# Sheet5.net
KiCad netlist of a schematic drawn in Altium Designer
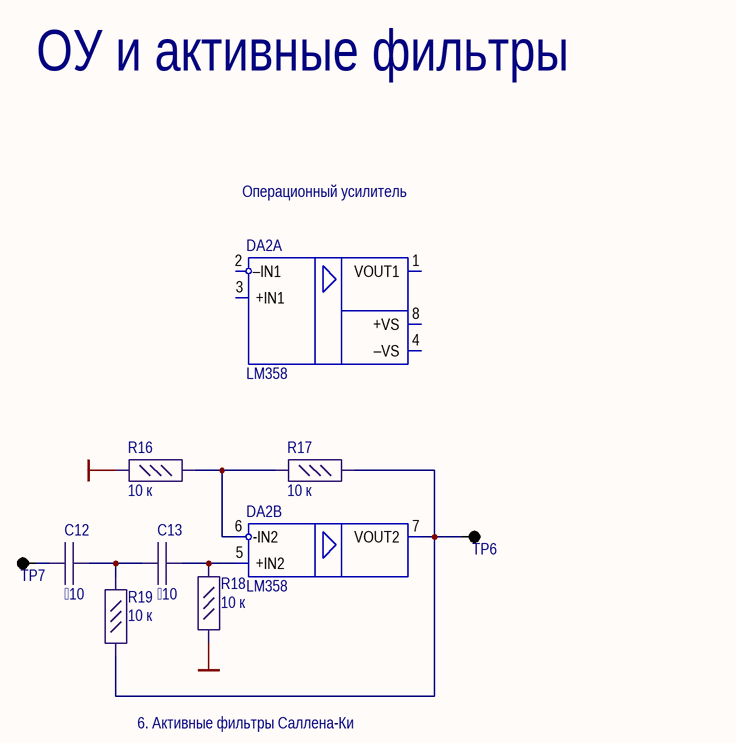
[diagram p0: Sheet5.SchDoc]

(export (version "E")
  (design (tool "Eeschema 10.0.6"))
  (components
    (comp (ref "C12")
      (value "10")
      (footprint "C_0603")
      (description "CAP CER 0.1UF 100V X7R 0603")
      (fields
        (field (name "PART NUMBER") "GRM188R72A104KA35D")
        (field (name "MANUFACTURER") "Murata Electronics")
      )
      (libsource (lib "Database_Lib") (part "Capasitor"))
    )
    (comp (ref "C13")
      (value "10")
      (footprint "C_0603")
      (description "CAP CER 0.1UF 100V X7R 0603")
      (fields
        (field (name "PART NUMBER") "GRM188R72A104KA35D")
        (field (name "MANUFACTURER") "Murata Electronics")
      )
      (libsource (lib "Database_Lib") (part "Capasitor"))
    )
    (comp (ref "DA2") (value "LM358") (footprint "SO-8") (libsource (lib "6.Chips") (part "LM358")))
    (comp (ref "R16")
      (value "10 к")
      (footprint "R_0603")
      (description "RES SMD 10K OHM 1% 1/10W 0603")
      (fields (field (name "PART NUMBER") "CR0603-FX-1002ELF") (field (name "MANUFACTURER") "Bourns Inc."))
      (libsource (lib "Database_Lib") (part "Resistor"))
    )
    (comp (ref "R17")
      (value "10 к")
      (footprint "R_0603")
      (description "RES SMD 10K OHM 1% 1/10W 0603")
      (fields (field (name "PART NUMBER") "CR0603-FX-1002ELF") (field (name "MANUFACTURER") "Bourns Inc."))
      (libsource (lib "Database_Lib") (part "Resistor"))
    )
    (comp (ref "R18")
      (value "10 к")
      (footprint "R_0603")
      (description "RES SMD 10K OHM 1% 1/10W 0603")
      (fields (field (name "PART NUMBER") "CR0603-FX-1002ELF") (field (name "MANUFACTURER") "Bourns Inc."))
      (libsource (lib "Database_Lib") (part "Resistor"))
    )
    (comp (ref "R19")
      (value "10 к")
      (footprint "R_0603")
      (description "RES SMD 10K OHM 1% 1/10W 0603")
      (fields (field (name "PART NUMBER") "CR0603-FX-1002ELF") (field (name "MANUFACTURER") "Bourns Inc."))
      (libsource (lib "Database_Lib") (part "Resistor"))
    )
    (comp (ref "TP6")
      (value "Test_Point_1")
      (footprint "Test_point")
      (libsource (lib "") (part "Test_Point_1_1"))
    )
    (comp (ref "TP7")
      (value "Test_Point_1")
      (footprint "Test_point")
      (libsource (lib "7.Connectors") (part "Test_Point_1"))
    )
  )
  (nets
    (net (code "1") (name "GND") (class "Default")
      (node (ref "R16") (pin "2") (pinfunction "2_2") (pintype "passive"))
      (node (ref "R18") (pin "2") (pinfunction "2_2") (pintype "passive"))
    )
    (net (code "2") (name "Net-(C12-Pad1)") (class "Default")
      (node (ref "C12") (pin "1") (pinfunction "1_1") (pintype "passive"))
      (node (ref "TP7") (pin "1") (pinfunction "1_1") (pintype "passive"))
    )
    (net (code "3") (name "Net-(C12-Pad2)") (class "Default")
      (node (ref "C12") (pin "2") (pinfunction "2_2") (pintype "passive"))
      (node (ref "C13") (pin "1") (pinfunction "1_1") (pintype "passive"))
      (node (ref "R19") (pin "1") (pinfunction "1_1") (pintype "passive"))
    )
    (net (code "4") (name "Net-(DA2B-+IN2)") (class "Default")
      (node (ref "C13") (pin "2") (pinfunction "2_2") (pintype "passive"))
      (node (ref "DA2") (pin "5") (pinfunction "+IN2_5") (pintype "passive"))
      (node (ref "R18") (pin "1") (pinfunction "1_1") (pintype "passive"))
    )
    (net (code "5") (name "Net-(DA2B--IN2)") (class "Default")
      (node (ref "DA2") (pin "6") (pinfunction "-IN2_6") (pintype "passive"))
      (node (ref "R16") (pin "1") (pinfunction "1_1") (pintype "passive"))
      (node (ref "R17") (pin "2") (pinfunction "2_2") (pintype "passive"))
    )
    (net (code "6") (name "Net-(DA2B-VOUT2)") (class "Default")
      (node (ref "DA2") (pin "7") (pinfunction "VOUT2_7") (pintype "passive"))
      (node (ref "R17") (pin "1") (pinfunction "1_1") (pintype "passive"))
      (node (ref "R19") (pin "2") (pinfunction "2_2") (pintype "passive"))
      (node (ref "TP6") (pin "1") (pinfunction "1_1") (pintype "passive"))
    )
    (net (code "7") (name "unconnected-(DA2A-+IN1-Pad3)") (class "Default")
      (node (ref "DA2") (pin "3") (pinfunction "+IN1_3") (pintype "passive"))
    )
    (net (code "8") (name "unconnected-(DA2A-+VS-Pad8)") (class "Default")
      (node (ref "DA2") (pin "8") (pinfunction "+VS_8") (pintype "passive"))
    )
    (net (code "9") (name "unconnected-(DA2A-VOUT1-Pad1)") (class "Default")
      (node (ref "DA2") (pin "1") (pinfunction "VOUT1_1") (pintype "passive"))
    )
    (net (code "10") (name "unconnected-(DA2A-–IN1-Pad2)") (class "Default")
      (node (ref "DA2") (pin "2") (pinfunction "–IN1_2") (pintype "passive"))
    )
    (net (code "11") (name "unconnected-(DA2A-–VS-Pad4)") (class "Default")
      (node (ref "DA2") (pin "4") (pinfunction "–VS_4") (pintype "passive"))
    )
  )
)
